# N64_Tx_V4_0.net
KiCad netlist of a schematic drawn in EAGLE
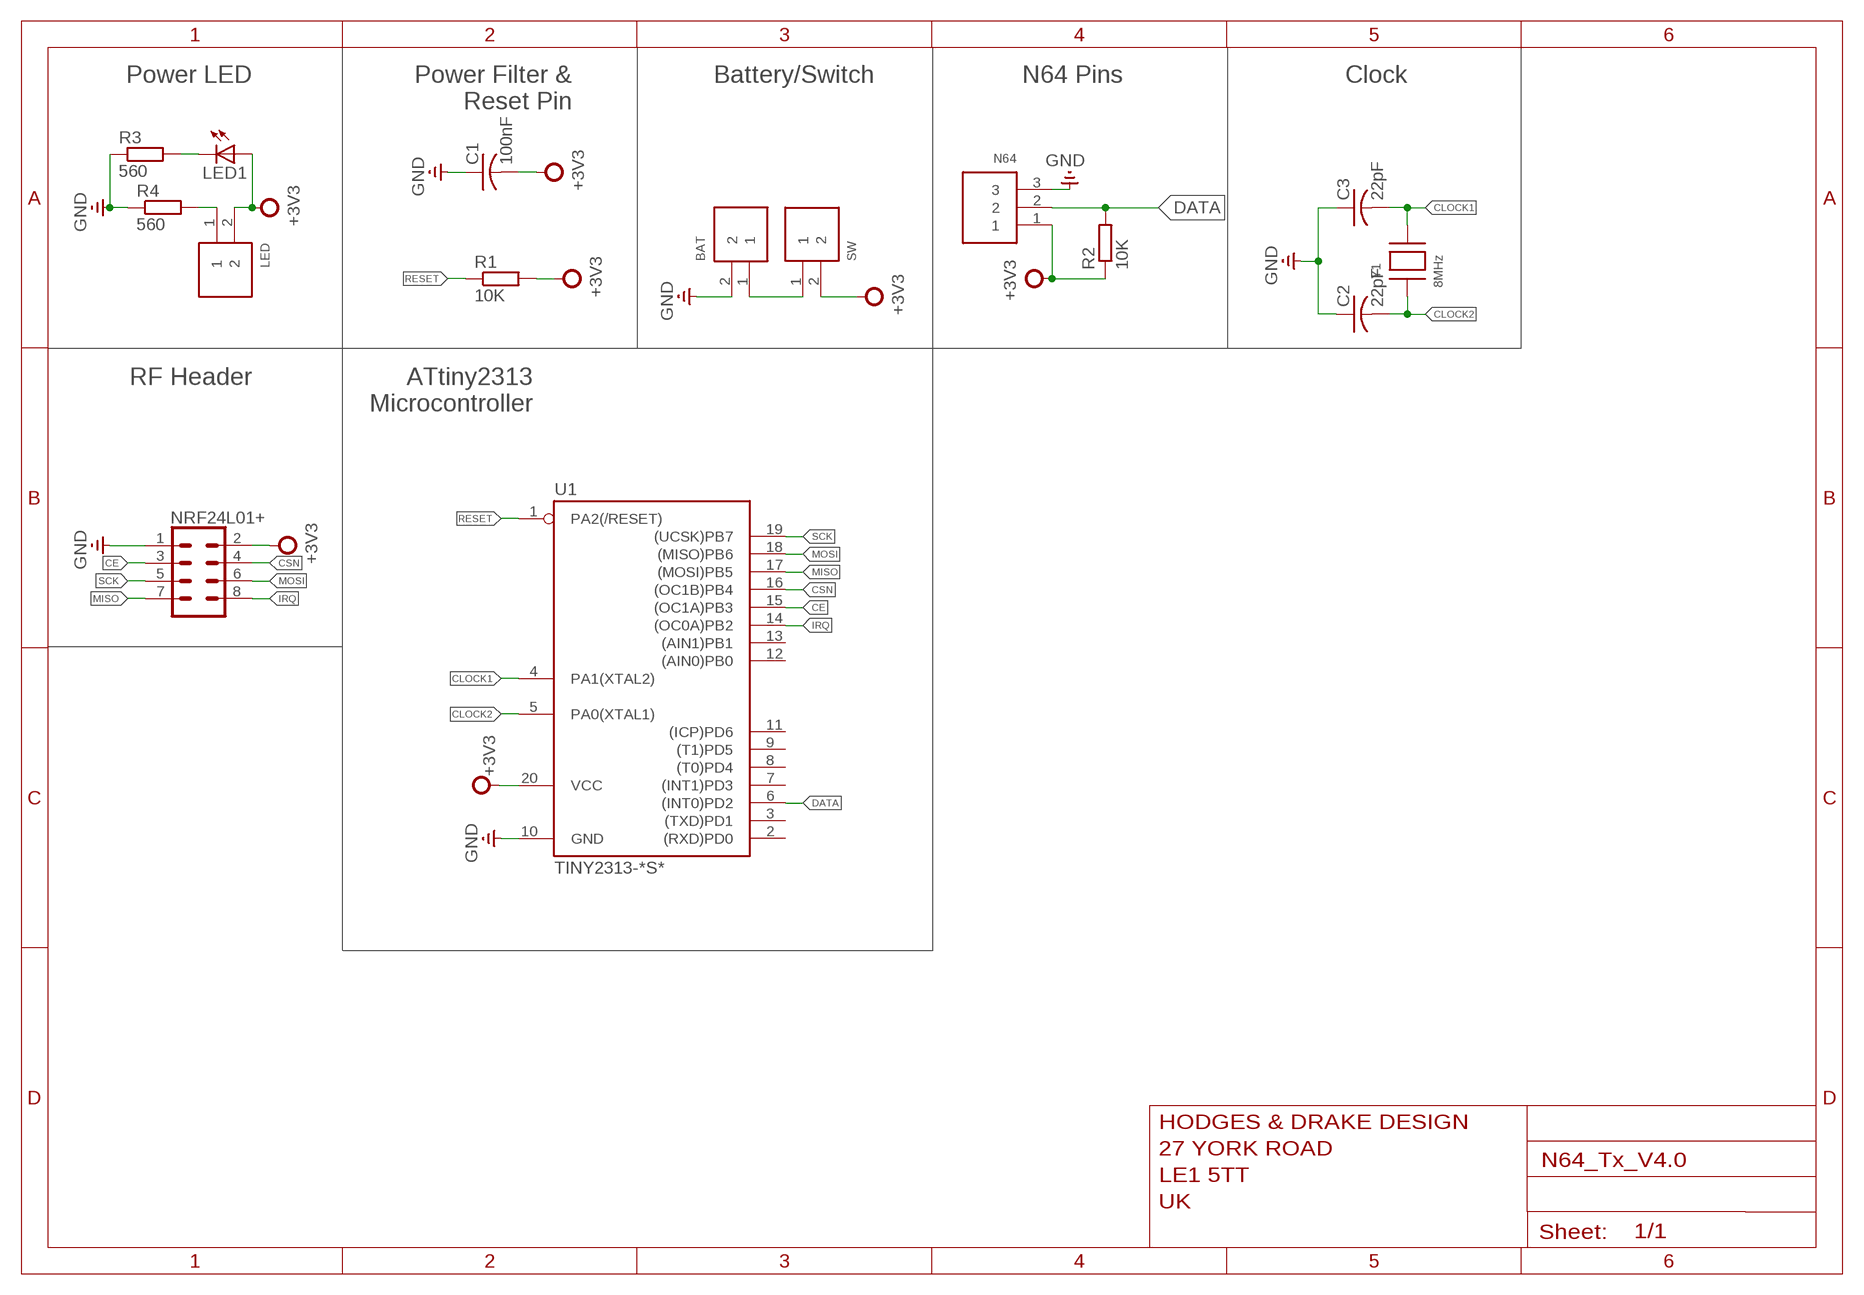
[diagram p0: schematic, sheet 1]

(export (version "E")
  (design (tool "Eeschema 10.0.6"))
  (components
    (comp (ref "BAT")
      (value "2PIN")
      (footprint "eagle-import:B2B-PH-K-S")
      (libsource (lib "eagle-import") (part "2PIN"))
    )
    (comp (ref "C1")
      (value "100nF")
      (footprint "eagle-import:C0603")
      (libsource (lib "eagle-import") (part "C-USC0603"))
    )
    (comp (ref "C2")
      (value "22pF")
      (footprint "eagle-import:C0603")
      (libsource (lib "eagle-import") (part "C-USC0603"))
    )
    (comp (ref "C3")
      (value "22pF")
      (footprint "eagle-import:C0603")
      (libsource (lib "eagle-import") (part "C-USC0603"))
    )
    (comp (ref "LED")
      (value "2PIN")
      (footprint "eagle-import:B2B-PH-K-S")
      (libsource (lib "eagle-import") (part "2PIN"))
    )
    (comp (ref "LED1")
      (value "LEDCHIPLED_0805")
      (footprint "eagle-import:CHIPLED_0805")
      (libsource (lib "eagle-import") (part "LEDCHIPLED_0805"))
    )
    (comp (ref "N64")
      (value "3PIN")
      (footprint "eagle-import:B3B-PH-K-S")
      (libsource (lib "eagle-import") (part "3PIN"))
    )
    (comp (ref "NRF24L01+")
      (value "CONN_04X2")
      (footprint "eagle-import:2X4")
      (libsource (lib "eagle-import") (part "CONN_04X2"))
    )
    (comp (ref "R1")
      (value "10K")
      (footprint "eagle-import:R0603")
      (libsource (lib "eagle-import") (part "R-0603"))
    )
    (comp (ref "R2")
      (value "10K")
      (footprint "eagle-import:R0603")
      (libsource (lib "eagle-import") (part "R-0603"))
    )
    (comp (ref "R3")
      (value "560")
      (footprint "eagle-import:R0603")
      (libsource (lib "eagle-import") (part "R-0603"))
    )
    (comp (ref "R4")
      (value "560")
      (footprint "eagle-import:R0603")
      (libsource (lib "eagle-import") (part "R-0603"))
    )
    (comp (ref "SW")
      (value "2PIN")
      (footprint "eagle-import:B2B-PH-K-S")
      (libsource (lib "eagle-import") (part "2PIN"))
    )
    (comp (ref "U1")
      (value "TINY2313-*S*")
      (footprint "eagle-import:SO20L$")
      (libsource (lib "eagle-import") (part "TINY2313-S"))
    )
    (comp (ref "Y1")
      (value "8MHz")
      (footprint "eagle-import:QANTEK_SMD_CRYSTAL_PACK")
      (libsource (lib "eagle-import") (part "QANTEK_SMD_CRYSTAL"))
    )
  )
  (nets
    (net (code "1") (name "+3V3") (class "Default")
      (node (ref "C1") (pin "2") (pinfunction "2_2") (pintype "passive"))
      (node (ref "LED") (pin "2") (pinfunction "2_2") (pintype "bidirectional"))
      (node (ref "LED1") (pin "A") (pinfunction "A_A") (pintype "passive"))
      (node (ref "N64") (pin "1") (pinfunction "1_1") (pintype "bidirectional"))
      (node (ref "NRF24L01+") (pin "2") (pinfunction "2_2") (pintype "passive"))
      (node (ref "R1") (pin "2") (pinfunction "2_2") (pintype "passive"))
      (node (ref "R2") (pin "1") (pinfunction "1_1") (pintype "passive"))
      (node (ref "SW") (pin "2") (pinfunction "2_2") (pintype "bidirectional"))
      (node (ref "U1") (pin "20") (pinfunction "VCC_20") (pintype "power_in"))
    )
    (net (code "2") (name "CE") (class "Default")
      (node (ref "NRF24L01+") (pin "3") (pinfunction "3_3") (pintype "passive"))
      (node (ref "U1") (pin "15") (pinfunction "(OC1A)PB3_15") (pintype "bidirectional"))
    )
    (net (code "3") (name "CLOCK1") (class "Default")
      (node (ref "C3") (pin "2") (pinfunction "2_2") (pintype "passive"))
      (node (ref "U1") (pin "4") (pinfunction "PA1(XTAL2)_4") (pintype "bidirectional"))
      (node (ref "Y1") (pin "P$2") (pinfunction "X2_P$2") (pintype "bidirectional"))
    )
    (net (code "4") (name "CLOCK2") (class "Default")
      (node (ref "C2") (pin "2") (pinfunction "2_2") (pintype "passive"))
      (node (ref "U1") (pin "5") (pinfunction "PA0(XTAL1)_5") (pintype "bidirectional"))
      (node (ref "Y1") (pin "P$1") (pinfunction "X1_P$1") (pintype "bidirectional"))
    )
    (net (code "5") (name "CSN") (class "Default")
      (node (ref "NRF24L01+") (pin "4") (pinfunction "4_4") (pintype "passive"))
      (node (ref "U1") (pin "16") (pinfunction "(OC1B)PB4_16") (pintype "bidirectional"))
    )
    (net (code "6") (name "DATA") (class "Default")
      (node (ref "N64") (pin "2") (pinfunction "2_2") (pintype "bidirectional"))
      (node (ref "R2") (pin "2") (pinfunction "2_2") (pintype "passive"))
      (node (ref "U1") (pin "6") (pinfunction "(INT0)PD2_6") (pintype "bidirectional"))
    )
    (net (code "7") (name "GND") (class "Default")
      (node (ref "BAT") (pin "2") (pinfunction "2_2") (pintype "bidirectional"))
      (node (ref "C1") (pin "1") (pinfunction "1_1") (pintype "passive"))
      (node (ref "C2") (pin "1") (pinfunction "1_1") (pintype "passive"))
      (node (ref "C3") (pin "1") (pinfunction "1_1") (pintype "passive"))
      (node (ref "N64") (pin "3") (pinfunction "3_3") (pintype "bidirectional"))
      (node (ref "NRF24L01+") (pin "1") (pinfunction "1_1") (pintype "passive"))
      (node (ref "R3") (pin "1") (pinfunction "1_1") (pintype "passive"))
      (node (ref "R4") (pin "1") (pinfunction "1_1") (pintype "passive"))
      (node (ref "U1") (pin "10") (pinfunction "GND_10") (pintype "power_in"))
    )
    (net (code "8") (name "IRQ") (class "Default")
      (node (ref "NRF24L01+") (pin "8") (pinfunction "8_8") (pintype "passive"))
      (node (ref "U1") (pin "14") (pinfunction "(OC0A)PB2_14") (pintype "bidirectional"))
    )
    (net (code "9") (name "MISO") (class "Default")
      (node (ref "NRF24L01+") (pin "7") (pinfunction "7_7") (pintype "passive"))
      (node (ref "U1") (pin "17") (pinfunction "(MOSI)PB5_17") (pintype "bidirectional"))
    )
    (net (code "10") (name "MOSI") (class "Default")
      (node (ref "NRF24L01+") (pin "6") (pinfunction "6_6") (pintype "passive"))
      (node (ref "U1") (pin "18") (pinfunction "(MISO)PB6_18") (pintype "bidirectional"))
    )
    (net (code "11") (name "Net-(BAT-Pad1)") (class "Default")
      (node (ref "BAT") (pin "1") (pinfunction "1_1") (pintype "bidirectional"))
      (node (ref "SW") (pin "1") (pinfunction "1_1") (pintype "bidirectional"))
    )
    (net (code "12") (name "Net-(LED-Pad1)") (class "Default")
      (node (ref "LED") (pin "1") (pinfunction "1_1") (pintype "bidirectional"))
      (node (ref "R4") (pin "2") (pinfunction "2_2") (pintype "passive"))
    )
    (net (code "13") (name "Net-(LED1-PadC)") (class "Default")
      (node (ref "LED1") (pin "C") (pinfunction "C_C") (pintype "passive"))
      (node (ref "R3") (pin "2") (pinfunction "2_2") (pintype "passive"))
    )
    (net (code "14") (name "RESET") (class "Default")
      (node (ref "R1") (pin "1") (pinfunction "1_1") (pintype "passive"))
      (node (ref "U1") (pin "1") (pinfunction "PA2(/RESET)_1") (pintype "input"))
    )
    (net (code "15") (name "SCK") (class "Default")
      (node (ref "NRF24L01+") (pin "5") (pinfunction "5_5") (pintype "passive"))
      (node (ref "U1") (pin "19") (pinfunction "(UCSK)PB7_19") (pintype "bidirectional"))
    )
    (net (code "16") (name "unconnected-(U1-(AIN0)PB0-Pad12)") (class "Default")
      (node (ref "U1") (pin "12") (pinfunction "(AIN0)PB0_12") (pintype "bidirectional"))
    )
    (net (code "17") (name "unconnected-(U1-(AIN1)PB1-Pad13)") (class "Default")
      (node (ref "U1") (pin "13") (pinfunction "(AIN1)PB1_13") (pintype "bidirectional"))
    )
    (net (code "18") (name "unconnected-(U1-(ICP)PD6-Pad11)") (class "Default")
      (node (ref "U1") (pin "11") (pinfunction "(ICP)PD6_11") (pintype "bidirectional"))
    )
    (net (code "19") (name "unconnected-(U1-(INT1)PD3-Pad7)") (class "Default")
      (node (ref "U1") (pin "7") (pinfunction "(INT1)PD3_7") (pintype "bidirectional"))
    )
    (net (code "20") (name "unconnected-(U1-(RXD)PD0-Pad2)") (class "Default")
      (node (ref "U1") (pin "2") (pinfunction "(RXD)PD0_2") (pintype "bidirectional"))
    )
    (net (code "21") (name "unconnected-(U1-(T0)PD4-Pad8)") (class "Default")
      (node (ref "U1") (pin "8") (pinfunction "(T0)PD4_8") (pintype "bidirectional"))
    )
    (net (code "22") (name "unconnected-(U1-(T1)PD5-Pad9)") (class "Default")
      (node (ref "U1") (pin "9") (pinfunction "(T1)PD5_9") (pintype "bidirectional"))
    )
    (net (code "23") (name "unconnected-(U1-(TXD)PD1-Pad3)") (class "Default")
      (node (ref "U1") (pin "3") (pinfunction "(TXD)PD1_3") (pintype "bidirectional"))
    )
  )
)
